# LED.net
KiCad netlist of a schematic drawn in Altium Designer
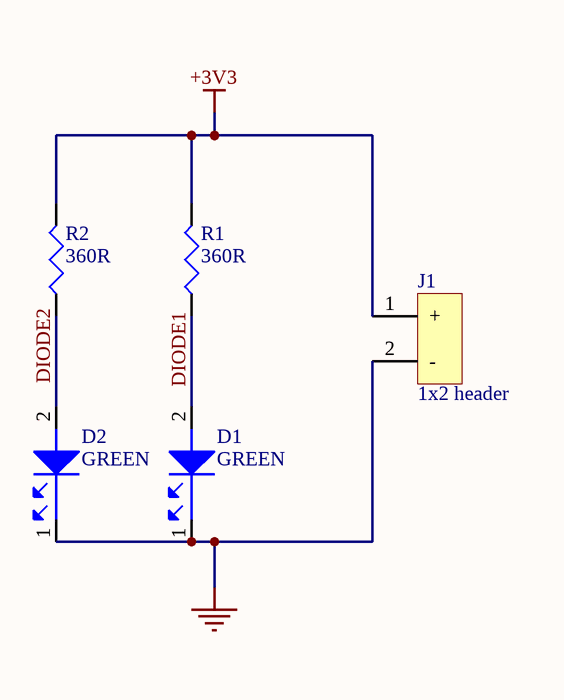
[diagram p0: LED.SchDoc]

(export (version "E")
  (design (tool "Eeschema 10.0.6"))
  (components
    (comp (ref "D1")
      (value "GREEN")
      (footprint "LED0603G")
      (description "Single Color LED, Yellow Green, Milky White, 1.2mm")
      (fields (field (name "MANUFACTURER") "Rohm") (field (name "MANUFACTURER PART NUMBER") "SML-512MWT86"))
      (libsource (lib "LED_Schlib") (part "SML-512MWT86"))
    )
    (comp (ref "D2")
      (value "GREEN")
      (footprint "LED0603G")
      (description "Single Color LED, Yellow Green, Milky White, 1.2mm")
      (fields (field (name "MANUFACTURER") "Rohm") (field (name "MANUFACTURER PART NUMBER") "SML-512MWT86"))
      (libsource (lib "LED_Schlib") (part "SML-512MWT86"))
    )
    (comp (ref "J1")
      (value "1x2 header")
      (footprint "HDR1X2")
      (fields (field (name "MANUFACTURER") "Molex") (field (name "MANUFACTURER PART NUMBER") "22-29-2021"))
      (libsource (lib "LED_Schlib") (part "22-29-2021"))
    )
    (comp (ref "R1")
      (value "360R")
      (footprint "R0805")
      (fields
        (field (name "MANUFACTURER") "Vishay")
        (field (name "MANUFACTURER PART NUMBER") "CRCW0805360RFKEA")
        (field (name "TOLERANCE") "1%")
      )
      (libsource (lib "LED_Schlib") (part "CRCW0805360RFKEA"))
    )
    (comp (ref "R2")
      (value "360R")
      (footprint "R0805")
      (fields
        (field (name "MANUFACTURER") "Vishay")
        (field (name "MANUFACTURER PART NUMBER") "CRCW0805360RFKEA")
        (field (name "TOLERANCE") "1%")
      )
      (libsource (lib "LED_Schlib") (part "CRCW0805360RFKEA"))
    )
  )
  (nets
    (net (code "1") (name "+3V3") (class "Default")
      (node (ref "J1") (pin "1") (pinfunction "+_1") (pintype "passive"))
      (node (ref "R1") (pin "2") (pinfunction "2_2") (pintype "passive"))
      (node (ref "R2") (pin "2") (pinfunction "2_2") (pintype "passive"))
    )
    (net (code "2") (name "/DIODE1") (class "Default")
      (node (ref "D1") (pin "2") (pinfunction "2_2") (pintype "passive"))
      (node (ref "R1") (pin "1") (pinfunction "1_1") (pintype "passive"))
    )
    (net (code "3") (name "/DIODE2") (class "Default")
      (node (ref "D2") (pin "2") (pinfunction "2_2") (pintype "passive"))
      (node (ref "R2") (pin "1") (pinfunction "1_1") (pintype "passive"))
    )
    (net (code "4") (name "GND") (class "Default")
      (node (ref "D1") (pin "1") (pinfunction "1_1") (pintype "passive"))
      (node (ref "D2") (pin "1") (pinfunction "1_1") (pintype "passive"))
      (node (ref "J1") (pin "2") (pinfunction "-_2") (pintype "passive"))
    )
  )
)
